# WIFI.net
KiCad netlist of a schematic drawn in Altium Designer
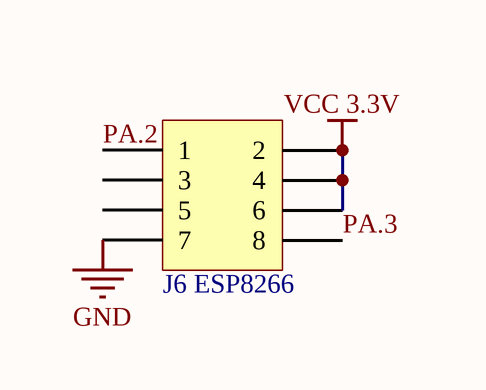
[diagram p0: WIFI.SchDoc]

(export (version "E")
  (design (tool "Eeschema 10.0.6"))
  (components
    (comp (ref "J6 ESP8266")
      (value "Header 4X2")
      (footprint "HDR2X4")
      (description "Header, 4-Pin, Dual row")
      (fields (field (name "PUBLISHER") "Altium Limited"))
      (libsource (lib "Miscellaneous Connectors") (part "Header 4X2"))
    )
  )
  (nets
    (net (code "1") (name "/PA.2") (class "Default")
      (node (ref "J6 ESP8266") (pin "1") (pinfunction "1_1") (pintype "passive"))
    )
    (net (code "2") (name "/PA.3") (class "Default")
      (node (ref "J6 ESP8266") (pin "8") (pinfunction "8_8") (pintype "passive"))
    )
    (net (code "3") (name "GND") (class "Default")
      (node (ref "J6 ESP8266") (pin "7") (pinfunction "7_7") (pintype "passive"))
    )
    (net (code "4") (name "VCC 3.3V") (class "Default")
      (node (ref "J6 ESP8266") (pin "2") (pinfunction "2_2") (pintype "passive"))
      (node (ref "J6 ESP8266") (pin "4") (pinfunction "4_4") (pintype "passive"))
      (node (ref "J6 ESP8266") (pin "6") (pinfunction "6_6") (pintype "passive"))
    )
    (net (code "5") (name "unconnected-(J6 ESP8266-Pad3)") (class "Default")
      (node (ref "J6 ESP8266") (pin "3") (pinfunction "3_3") (pintype "passive"))
    )
    (net (code "6") (name "unconnected-(J6 ESP8266-Pad5)") (class "Default")
      (node (ref "J6 ESP8266") (pin "5") (pinfunction "5_5") (pintype "passive"))
    )
  )
)
